# S7CAS-PLEIADES-CARTE-MERE_P01_CAN.net
KiCad netlist of a schematic drawn in Altium Designer
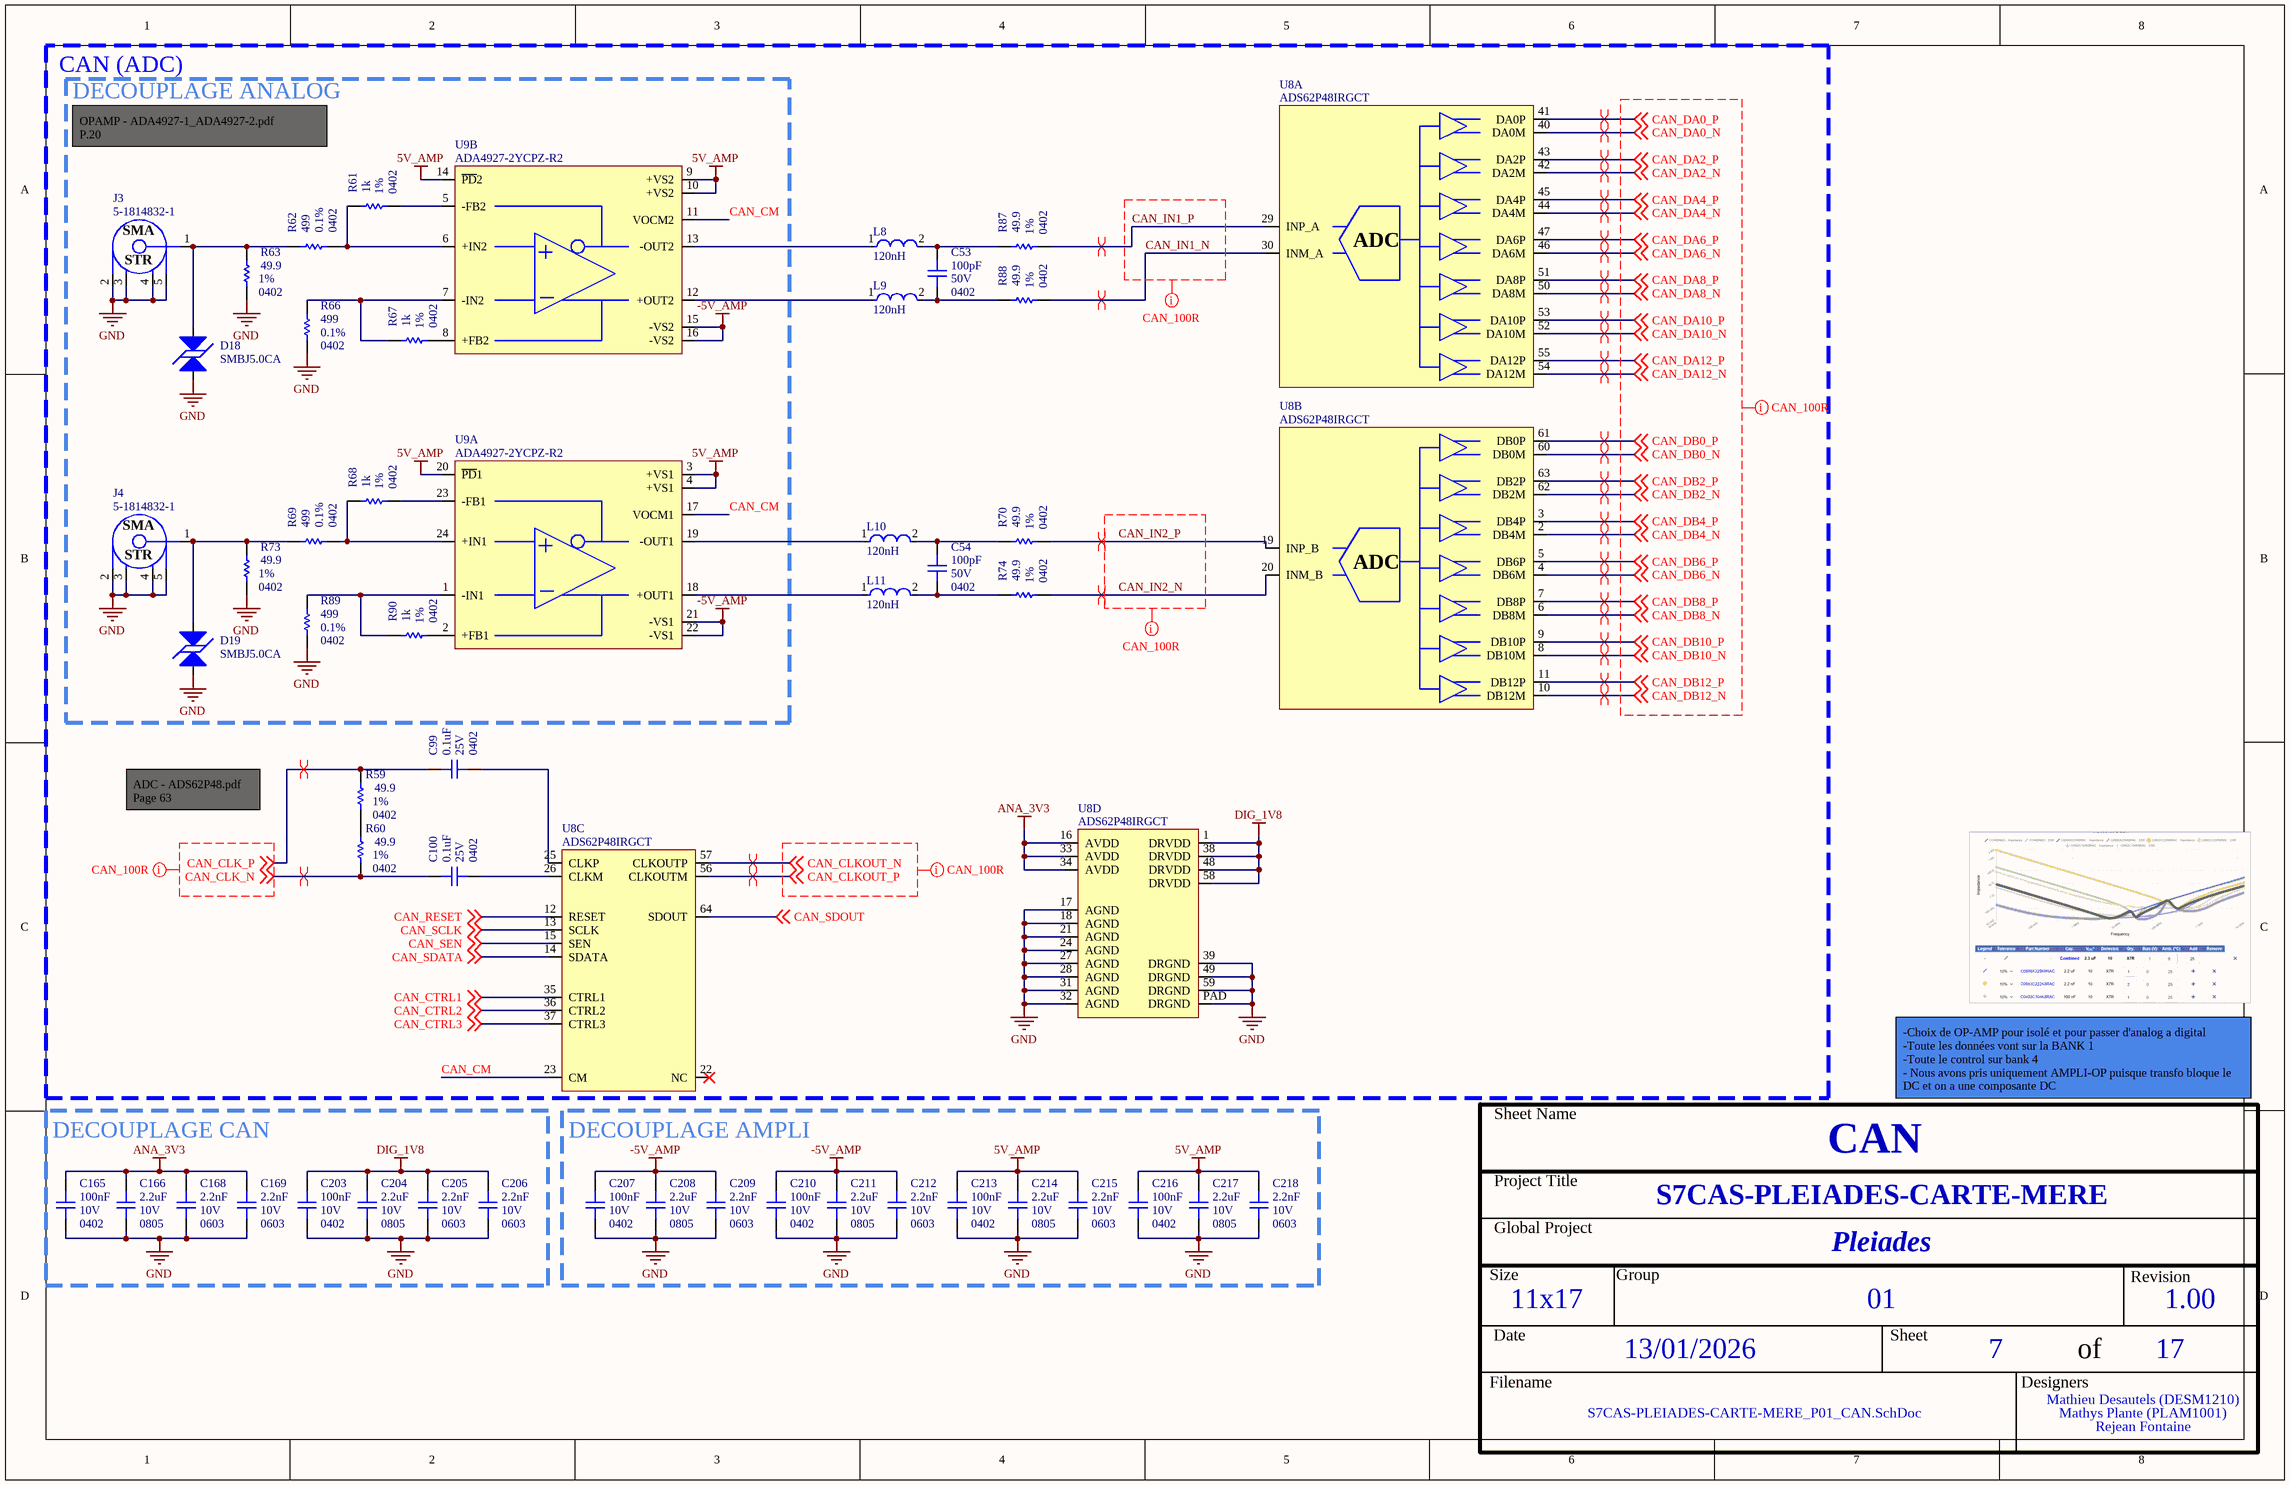
[diagram p0: S7CAS-PLEIADES-CARTE-MERE_P01_CAN.SchDoc]

(export (version "E")
  (design (tool "Eeschema 10.0.6"))
  (components
    (comp (ref "C53")
      (value "100pF")
      (footprint "CAP_0402")
      (description "100 pF ±5% 50V Ceramic Capacitor C0G, NP0 0603 (1608 Metric)")
      (fields
        (field (name "MFG") "Murata Electronics")
        (field (name "MFG PART NUMBER") "GRM1885C1H101JA01D")
        (field (name "VOLTAGE") "50V")
        (field (name "PACKAGE") "0402")
        (field (name "CREATEDBY") "Jonathan Bouchard")
      )
      (libsource (lib "s7cas_lib2023") (part "CAP - 0402"))
    )
    (comp (ref "C54")
      (value "100pF")
      (footprint "CAP_0402")
      (description "100 pF ±5% 50V Ceramic Capacitor C0G, NP0 0603 (1608 Metric)")
      (fields
        (field (name "MFG") "Murata Electronics")
        (field (name "MFG PART NUMBER") "GRM1885C1H101JA01D")
        (field (name "VOLTAGE") "50V")
        (field (name "PACKAGE") "0402")
        (field (name "CREATEDBY") "Jonathan Bouchard")
      )
      (libsource (lib "s7cas_lib2023") (part "CAP - 0402"))
    )
    (comp (ref "C99")
      (value "0.1uF")
      (footprint "CAP_0402")
      (description "0.1 µF ±10% 25V Ceramic Capacitor X7R 0402 (1005 Metric)")
      (fields
        (field (name "MFG") "Samsung Electro-Mechanics")
        (field (name "MFG PART NUMBER") "CL05B104KA5NNNC")
        (field (name "VOLTAGE") "25V")
        (field (name "PACKAGE") "0402")
        (field (name "CREATEDBY") "Jonathan Bouchard")
      )
      (libsource (lib "s7cas_lib2023") (part "CAP - 0402"))
    )
    (comp (ref "C100")
      (value "0.1uF")
      (footprint "CAP_0402")
      (description "0.1 µF ±10% 25V Ceramic Capacitor X7R 0402 (1005 Metric)")
      (fields
        (field (name "MFG") "Samsung Electro-Mechanics")
        (field (name "MFG PART NUMBER") "CL05B104KA5NNNC")
        (field (name "VOLTAGE") "25V")
        (field (name "PACKAGE") "0402")
        (field (name "CREATEDBY") "Jonathan Bouchard")
      )
      (libsource (lib "s7cas_lib2023") (part "CAP - 0402"))
    )
    (comp (ref "C165")
      (value "100nF")
      (footprint "CAP_0402")
      (description "CAP - 0402")
      (fields
        (field (name "MFG PART NUMBER") "C0402C104K8RAC")
        (field (name "VOLTAGE") "10V")
        (field (name "PACKAGE") "0402")
        (field (name "CREATEDBY") "Jonathan Bouchard")
      )
      (libsource (lib "s7cas_lib2023") (part "CAP - 0402"))
    )
    (comp (ref "C166")
      (value "2.2uF")
      (footprint "CAP_0805")
      (description "CAP - 0805")
      (fields
        (field (name "MFG PART NUMBER") "C0805C225K8RAC")
        (field (name "VOLTAGE") "10V")
        (field (name "PACKAGE") "0805")
        (field (name "CREATEDBY") "Jonathan Bouchard")
      )
      (libsource (lib "s7cas_lib2023") (part "CAP - 0805"))
    )
    (comp (ref "C168")
      (value "2.2nF")
      (footprint "CAP_0603")
      (description "CAP - 0603")
      (fields
        (field (name "MFG PART NUMBER") "C0603X222K8RAC")
        (field (name "VOLTAGE") "10V")
        (field (name "PACKAGE") "0603")
        (field (name "CREATEDBY") "Jonathan Bouchard")
      )
      (libsource (lib "s7cas_lib2023") (part "CAP - 0603"))
    )
    (comp (ref "C169")
      (value "2.2nF")
      (footprint "CAP_0603")
      (description "CAP - 0603")
      (fields
        (field (name "MFG PART NUMBER") "C0603X222K8RAC")
        (field (name "VOLTAGE") "10V")
        (field (name "PACKAGE") "0603")
        (field (name "CREATEDBY") "Jonathan Bouchard")
      )
      (libsource (lib "s7cas_lib2023") (part "CAP - 0603"))
    )
    (comp (ref "C203")
      (value "100nF")
      (footprint "CAP_0402")
      (description "CAP - 0402")
      (fields
        (field (name "MFG PART NUMBER") "C0402C104K8RAC")
        (field (name "VOLTAGE") "10V")
        (field (name "PACKAGE") "0402")
        (field (name "CREATEDBY") "Jonathan Bouchard")
      )
      (libsource (lib "s7cas_lib2023") (part "CAP - 0402"))
    )
    (comp (ref "C204")
      (value "2.2uF")
      (footprint "CAP_0805")
      (description "CAP - 0805")
      (fields
        (field (name "MFG PART NUMBER") "C0805C225K8RAC")
        (field (name "VOLTAGE") "10V")
        (field (name "PACKAGE") "0805")
        (field (name "CREATEDBY") "Jonathan Bouchard")
      )
      (libsource (lib "s7cas_lib2023") (part "CAP - 0805"))
    )
    (comp (ref "C205")
      (value "2.2nF")
      (footprint "CAP_0603")
      (description "CAP - 0603")
      (fields
        (field (name "MFG PART NUMBER") "C0603X222K8RAC")
        (field (name "VOLTAGE") "10V")
        (field (name "PACKAGE") "0603")
        (field (name "CREATEDBY") "Jonathan Bouchard")
      )
      (libsource (lib "s7cas_lib2023") (part "CAP - 0603"))
    )
    (comp (ref "C206")
      (value "2.2nF")
      (footprint "CAP_0603")
      (description "CAP - 0603")
      (fields
        (field (name "MFG PART NUMBER") "C0603X222K8RAC")
        (field (name "VOLTAGE") "10V")
        (field (name "PACKAGE") "0603")
        (field (name "CREATEDBY") "Jonathan Bouchard")
      )
      (libsource (lib "s7cas_lib2023") (part "CAP - 0603"))
    )
    (comp (ref "C207")
      (value "100nF")
      (footprint "CAP_0402")
      (description "CAP - 0402")
      (fields
        (field (name "MFG PART NUMBER") "C0402C104K8RAC")
        (field (name "VOLTAGE") "10V")
        (field (name "PACKAGE") "0402")
        (field (name "CREATEDBY") "Jonathan Bouchard")
      )
      (libsource (lib "s7cas_lib2023") (part "CAP - 0402"))
    )
    (comp (ref "C208")
      (value "2.2uF")
      (footprint "CAP_0805")
      (description "CAP - 0805")
      (fields
        (field (name "MFG PART NUMBER") "C0805C225K8RAC")
        (field (name "VOLTAGE") "10V")
        (field (name "PACKAGE") "0805")
        (field (name "CREATEDBY") "Jonathan Bouchard")
      )
      (libsource (lib "s7cas_lib2023") (part "CAP - 0805"))
    )
    (comp (ref "C209")
      (value "2.2nF")
      (footprint "CAP_0603")
      (description "CAP - 0603")
      (fields
        (field (name "MFG PART NUMBER") "C0603X222K8RAC")
        (field (name "VOLTAGE") "10V")
        (field (name "PACKAGE") "0603")
        (field (name "CREATEDBY") "Jonathan Bouchard")
      )
      (libsource (lib "s7cas_lib2023") (part "CAP - 0603"))
    )
    (comp (ref "C210")
      (value "100nF")
      (footprint "CAP_0402")
      (description "CAP - 0402")
      (fields
        (field (name "MFG PART NUMBER") "C0402C104K8RAC")
        (field (name "VOLTAGE") "10V")
        (field (name "PACKAGE") "0402")
        (field (name "CREATEDBY") "Jonathan Bouchard")
      )
      (libsource (lib "s7cas_lib2023") (part "CAP - 0402"))
    )
    (comp (ref "C211")
      (value "2.2uF")
      (footprint "CAP_0805")
      (description "CAP - 0805")
      (fields
        (field (name "MFG PART NUMBER") "C0805C225K8RAC")
        (field (name "VOLTAGE") "10V")
        (field (name "PACKAGE") "0805")
        (field (name "CREATEDBY") "Jonathan Bouchard")
      )
      (libsource (lib "s7cas_lib2023") (part "CAP - 0805"))
    )
    (comp (ref "C212")
      (value "2.2nF")
      (footprint "CAP_0603")
      (description "CAP - 0603")
      (fields
        (field (name "MFG PART NUMBER") "C0603X222K8RAC")
        (field (name "VOLTAGE") "10V")
        (field (name "PACKAGE") "0603")
        (field (name "CREATEDBY") "Jonathan Bouchard")
      )
      (libsource (lib "s7cas_lib2023") (part "CAP - 0603"))
    )
    (comp (ref "C213")
      (value "100nF")
      (footprint "CAP_0402")
      (description "CAP - 0402")
      (fields
        (field (name "MFG PART NUMBER") "C0402C104K8RAC")
        (field (name "VOLTAGE") "10V")
        (field (name "PACKAGE") "0402")
        (field (name "CREATEDBY") "Jonathan Bouchard")
      )
      (libsource (lib "s7cas_lib2023") (part "CAP - 0402"))
    )
    (comp (ref "C214")
      (value "2.2uF")
      (footprint "CAP_0805")
      (description "CAP - 0805")
      (fields
        (field (name "MFG PART NUMBER") "C0805C225K8RAC")
        (field (name "VOLTAGE") "10V")
        (field (name "PACKAGE") "0805")
        (field (name "CREATEDBY") "Jonathan Bouchard")
      )
      (libsource (lib "s7cas_lib2023") (part "CAP - 0805"))
    )
    (comp (ref "C215")
      (value "2.2nF")
      (footprint "CAP_0603")
      (description "CAP - 0603")
      (fields
        (field (name "MFG PART NUMBER") "C0603X222K8RAC")
        (field (name "VOLTAGE") "10V")
        (field (name "PACKAGE") "0603")
        (field (name "CREATEDBY") "Jonathan Bouchard")
      )
      (libsource (lib "s7cas_lib2023") (part "CAP - 0603"))
    )
    (comp (ref "C216")
      (value "100nF")
      (footprint "CAP_0402")
      (description "CAP - 0402")
      (fields
        (field (name "MFG PART NUMBER") "C0402C104K8RAC")
        (field (name "VOLTAGE") "10V")
        (field (name "PACKAGE") "0402")
        (field (name "CREATEDBY") "Jonathan Bouchard")
      )
      (libsource (lib "s7cas_lib2023") (part "CAP - 0402"))
    )
    (comp (ref "C217")
      (value "2.2uF")
      (footprint "CAP_0805")
      (description "CAP - 0805")
      (fields
        (field (name "MFG PART NUMBER") "C0805C225K8RAC")
        (field (name "VOLTAGE") "10V")
        (field (name "PACKAGE") "0805")
        (field (name "CREATEDBY") "Jonathan Bouchard")
      )
      (libsource (lib "s7cas_lib2023") (part "CAP - 0805"))
    )
    (comp (ref "C218")
      (value "2.2nF")
      (footprint "CAP_0603")
      (description "CAP - 0603")
      (fields
        (field (name "MFG PART NUMBER") "C0603X222K8RAC")
        (field (name "VOLTAGE") "10V")
        (field (name "PACKAGE") "0603")
        (field (name "CREATEDBY") "Jonathan Bouchard")
      )
      (libsource (lib "s7cas_lib2023") (part "CAP - 0603"))
    )
    (comp (ref "D18")
      (value "SMBJ5.0CA")
      (footprint "TVS_PWR_SMBJ5.0CA")
      (description "TVS - BIDIR 5V 9.2V 600W - DO214AA")
      (fields
        (field (name "CREATEDBY/DATE") "Jonathan Bouchard - 2019-03-22")
        (field (name "VERIFIEDBY") "Nicolas V. (2019-05-06)")
      )
      (libsource (lib "s7cas_lib2023") (part "TVS_PWR_SMBJ5.0CA"))
    )
    (comp (ref "D19")
      (value "SMBJ5.0CA")
      (footprint "TVS_PWR_SMBJ5.0CA")
      (description "TVS - BIDIR 5V 9.2V 600W - DO214AA")
      (fields
        (field (name "CREATEDBY/DATE") "Jonathan Bouchard - 2019-03-22")
        (field (name "VERIFIEDBY") "Nicolas V. (2019-05-06)")
      )
      (libsource (lib "s7cas_lib2023") (part "TVS_PWR_SMBJ5.0CA"))
    )
    (comp (ref "J3")
      (value "5-1814832-1")
      (footprint "CONN_SMA_5-1814832-1")
      (description "CONN -  SMA JACK STR 50 OHM - TH")
      (fields
        (field (name "MFG") "TE Connectivity AMP Connectors")
        (field (name "CREATEDBY") "Jonathan Bouchard")
      )
      (libsource (lib "s7cas_lib2023") (part "CONN_SMA_5-1814832-1"))
    )
    (comp (ref "J4")
      (value "5-1814832-1")
      (footprint "CONN_SMA_5-1814832-1")
      (description "CONN -  SMA JACK STR 50 OHM - TH")
      (fields
        (field (name "MFG") "TE Connectivity AMP Connectors")
        (field (name "CREATEDBY") "Jonathan Bouchard")
      )
      (libsource (lib "s7cas_lib2023") (part "CONN_SMA_5-1814832-1"))
    )
    (comp (ref "L8")
      (value "120nH")
      (footprint "FP-0603HP-MFG")
      (description "High Q Ceramic Chip Inductors 3.3nH 5% 0.024Ohm 1900mA 0603")
      (fields (field (name "TOLERANCE") "5%"))
      (libsource (lib "Altium Content Vault") (part "725321dda6339637d4d059423bc1c3c"))
    )
    (comp (ref "L9")
      (value "120nH")
      (footprint "FP-0603HP-MFG")
      (description "High Q Ceramic Chip Inductors 3.3nH 5% 0.024Ohm 1900mA 0603")
      (fields (field (name "TOLERANCE") "5%"))
      (libsource (lib "Altium Content Vault") (part "725321dda6339637d4d059423bc1c3c"))
    )
    (comp (ref "L10")
      (value "120nH")
      (footprint "FP-0603HP-MFG")
      (description "High Q Ceramic Chip Inductors 3.3nH 5% 0.024Ohm 1900mA 0603")
      (fields (field (name "TOLERANCE") "5%"))
      (libsource (lib "Altium Content Vault") (part "725321dda6339637d4d059423bc1c3c"))
    )
    (comp (ref "L11")
      (value "120nH")
      (footprint "FP-0603HP-MFG")
      (description "High Q Ceramic Chip Inductors 3.3nH 5% 0.024Ohm 1900mA 0603")
      (fields (field (name "TOLERANCE") "5%"))
      (libsource (lib "Altium Content Vault") (part "725321dda6339637d4d059423bc1c3c"))
    )
    (comp (ref "R59")
      (value "49.9")
      (footprint "RES_0402")
      (description "49.9 Ohms ±1% 0.1W, 1/10W Chip Resistor 0402 (1005 Metric) Automotive AEC-Q200 Thick Film")
      (fields
        (field (name "VOLTAGE") "75V")
        (field (name "MFG") "Vishay Dale")
        (field (name "PACKAGE") "0402")
        (field (name "PRECISION") "1%")
        (field (name "CREATEDBY") "Jonathan Bouchard")
      )
      (libsource (lib "s7cas_lib2023") (part "RES - 0402"))
    )
    (comp (ref "R60")
      (value "49.9")
      (footprint "RES_0402")
      (description "49.9 Ohms ±1% 0.1W, 1/10W Chip Resistor 0402 (1005 Metric) Automotive AEC-Q200 Thick Film")
      (fields
        (field (name "VOLTAGE") "75V")
        (field (name "MFG") "Vishay Dale")
        (field (name "PACKAGE") "0402")
        (field (name "PRECISION") "1%")
        (field (name "CREATEDBY") "Jonathan Bouchard")
      )
      (libsource (lib "s7cas_lib2023") (part "RES - 0402"))
    )
    (comp (ref "R61")
      (value "1k")
      (footprint "RES_0402")
      (description "1 kOhms ±1% 0.1W, 1/10W Chip Resistor 0402 (1005 Metric) Automotive AEC-Q200 Thick Film")
      (fields
        (field (name "VOLTAGE") "50V")
        (field (name "MFG") "Panasonic Electronic Components")
        (field (name "PACKAGE") "0402")
        (field (name "PRECISION") "1%")
        (field (name "CREATEDBY") "Jonathan Bouchard")
      )
      (libsource (lib "s7cas_lib2023") (part "RES - 0402"))
    )
    (comp (ref "R62")
      (value "499")
      (footprint "RES_0402")
      (description "499 Ohms ±0.1% 0.063W, 1/16W Chip Resistor 0402 (1005 Metric) Automotive AEC-Q200 Thin Film")
      (fields
        (field (name "VOLTAGE") "TBD")
        (field (name "MFG") "Panasonic Electronic Components")
        (field (name "PACKAGE") "0402")
        (field (name "PRECISION") "0.1%")
        (field (name "CREATEDBY") "Jonathan Bouchard")
      )
      (libsource (lib "s7cas_lib2023") (part "RES - 0402"))
    )
    (comp (ref "R63")
      (value "49.9")
      (footprint "RES_0402")
      (description "49.9 Ohms ±1% 0.1W, 1/10W Chip Resistor 0402 (1005 Metric) Automotive AEC-Q200 Thick Film")
      (fields
        (field (name "VOLTAGE") "75V")
        (field (name "MFG") "Vishay Dale")
        (field (name "PACKAGE") "0402")
        (field (name "PRECISION") "1%")
        (field (name "CREATEDBY") "Jonathan Bouchard")
      )
      (libsource (lib "s7cas_lib2023") (part "RES - 0402"))
    )
    (comp (ref "R66")
      (value "499")
      (footprint "RES_0402")
      (description "499 Ohms ±0.1% 0.063W, 1/16W Chip Resistor 0402 (1005 Metric) Automotive AEC-Q200 Thin Film")
      (fields
        (field (name "VOLTAGE") "TBD")
        (field (name "MFG") "Panasonic Electronic Components")
        (field (name "PACKAGE") "0402")
        (field (name "PRECISION") "0.1%")
        (field (name "CREATEDBY") "Jonathan Bouchard")
      )
      (libsource (lib "s7cas_lib2023") (part "RES - 0402"))
    )
    (comp (ref "R67")
      (value "1k")
      (footprint "RES_0402")
      (description "1 kOhms ±1% 0.1W, 1/10W Chip Resistor 0402 (1005 Metric) Automotive AEC-Q200 Thick Film")
      (fields
        (field (name "VOLTAGE") "50V")
        (field (name "MFG") "Panasonic Electronic Components")
        (field (name "PACKAGE") "0402")
        (field (name "PRECISION") "1%")
        (field (name "CREATEDBY") "Jonathan Bouchard")
      )
      (libsource (lib "s7cas_lib2023") (part "RES - 0402"))
    )
    (comp (ref "R68")
      (value "1k")
      (footprint "RES_0402")
      (description "1 kOhms ±1% 0.1W, 1/10W Chip Resistor 0402 (1005 Metric) Automotive AEC-Q200 Thick Film")
      (fields
        (field (name "VOLTAGE") "50V")
        (field (name "MFG") "Panasonic Electronic Components")
        (field (name "PACKAGE") "0402")
        (field (name "PRECISION") "1%")
        (field (name "CREATEDBY") "Jonathan Bouchard")
      )
      (libsource (lib "s7cas_lib2023") (part "RES - 0402"))
    )
    (comp (ref "R69")
      (value "499")
      (footprint "RES_0402")
      (description "499 Ohms ±0.1% 0.063W, 1/16W Chip Resistor 0402 (1005 Metric) Automotive AEC-Q200 Thin Film")
      (fields
        (field (name "VOLTAGE") "TBD")
        (field (name "MFG") "Panasonic Electronic Components")
        (field (name "PACKAGE") "0402")
        (field (name "PRECISION") "0.1%")
        (field (name "CREATEDBY") "Jonathan Bouchard")
      )
      (libsource (lib "s7cas_lib2023") (part "RES - 0402"))
    )
    (comp (ref "R70")
      (value "49.9")
      (footprint "RES_0402")
      (description "49.9 Ohms ±1% 0.1W, 1/10W Chip Resistor 0402 (1005 Metric) Automotive AEC-Q200 Thick Film")
      (fields
        (field (name "VOLTAGE") "75V")
        (field (name "MFG") "Vishay Dale")
        (field (name "PACKAGE") "0402")
        (field (name "PRECISION") "1%")
        (field (name "CREATEDBY") "Jonathan Bouchard")
      )
      (libsource (lib "s7cas_lib2023") (part "RES - 0402"))
    )
    (comp (ref "R73")
      (value "49.9")
      (footprint "RES_0402")
      (description "49.9 Ohms ±1% 0.1W, 1/10W Chip Resistor 0402 (1005 Metric) Automotive AEC-Q200 Thick Film")
      (fields
        (field (name "VOLTAGE") "75V")
        (field (name "MFG") "Vishay Dale")
        (field (name "PACKAGE") "0402")
        (field (name "PRECISION") "1%")
        (field (name "CREATEDBY") "Jonathan Bouchard")
      )
      (libsource (lib "s7cas_lib2023") (part "RES - 0402"))
    )
    (comp (ref "R74")
      (value "49.9")
      (footprint "RES_0402")
      (description "49.9 Ohms ±1% 0.1W, 1/10W Chip Resistor 0402 (1005 Metric) Automotive AEC-Q200 Thick Film")
      (fields
        (field (name "VOLTAGE") "75V")
        (field (name "MFG") "Vishay Dale")
        (field (name "PACKAGE") "0402")
        (field (name "PRECISION") "1%")
        (field (name "CREATEDBY") "Jonathan Bouchard")
      )
      (libsource (lib "s7cas_lib2023") (part "RES - 0402"))
    )
    (comp (ref "R87")
      (value "49.9")
      (footprint "RES_0402")
      (description "49.9 Ohms ±1% 0.1W, 1/10W Chip Resistor 0402 (1005 Metric) Automotive AEC-Q200 Thick Film")
      (fields
        (field (name "VOLTAGE") "75V")
        (field (name "MFG") "Vishay Dale")
        (field (name "PACKAGE") "0402")
        (field (name "PRECISION") "1%")
        (field (name "CREATEDBY") "Jonathan Bouchard")
      )
      (libsource (lib "s7cas_lib2023") (part "RES - 0402"))
    )
    (comp (ref "R88")
      (value "49.9")
      (footprint "RES_0402")
      (description "49.9 Ohms ±1% 0.1W, 1/10W Chip Resistor 0402 (1005 Metric) Automotive AEC-Q200 Thick Film")
      (fields
        (field (name "VOLTAGE") "75V")
        (field (name "MFG") "Vishay Dale")
        (field (name "PACKAGE") "0402")
        (field (name "PRECISION") "1%")
        (field (name "CREATEDBY") "Jonathan Bouchard")
      )
      (libsource (lib "s7cas_lib2023") (part "RES - 0402"))
    )
    (comp (ref "R89")
      (value "499")
      (footprint "RES_0402")
      (description "499 Ohms ±0.1% 0.063W, 1/16W Chip Resistor 0402 (1005 Metric) Automotive AEC-Q200 Thin Film")
      (fields
        (field (name "VOLTAGE") "TBD")
        (field (name "MFG") "Panasonic Electronic Components")
        (field (name "PACKAGE") "0402")
        (field (name "PRECISION") "0.1%")
        (field (name "CREATEDBY") "Jonathan Bouchard")
      )
      (libsource (lib "s7cas_lib2023") (part "RES - 0402"))
    )
    (comp (ref "R90")
      (value "1k")
      (footprint "RES_0402")
      (description "1 kOhms ±1% 0.1W, 1/10W Chip Resistor 0402 (1005 Metric) Automotive AEC-Q200 Thick Film")
      (fields
        (field (name "VOLTAGE") "50V")
        (field (name "MFG") "Panasonic Electronic Components")
        (field (name "PACKAGE") "0402")
        (field (name "PRECISION") "1%")
        (field (name "CREATEDBY") "Jonathan Bouchard")
      )
      (libsource (lib "s7cas_lib2023") (part "RES - 0402"))
    )
    (comp (ref "U8")
      (value "ADS62P48IRGCT")
      (footprint "ADC_ADS62P48IRGCT")
      (description "ADC - 14 BIT 210MSPS SUAL - VQFN-64")
      (fields
        (field (name "VOLTAGE") "3.15 V ~ 3.6 V / 1.7 V ~ 1.9 V")
        (field (name "MFG") "Texas Instruments")
        (field (name "CREATEDBY") "Jonathan Bouchard")
      )
      (libsource (lib "s7cas_lib2023") (part "ADC_ADS62P48IRGCT"))
    )
    (comp (ref "U9")
      (value "ADA4927-2YCPZ-R2")
      (footprint "OPAMP_ADA4927-2YCPZ-R2")
      (description "OPAMP - CFA 2.3GHZ - QFN-24")
      (fields
        (field (name "VOLTAGE") "4.5 V ~ 11 V, ±2.25 V ~ 5.5 V")
        (field (name "MFG") "Analog Devices")
        (field (name "CREATEDBY") "Jonathan Bouchard")
      )
      (libsource (lib "s7cas_lib2023") (part "OPAMP_ADA4927-2YCPZ-R2"))
    )
  )
  (nets
    (net (code "1") (name "-5V_AMP") (class "Default")
      (node (ref "C207") (pin "2") (pinfunction "2_2") (pintype "passive"))
      (node (ref "C208") (pin "2") (pinfunction "2_2") (pintype "passive"))
      (node (ref "C209") (pin "2") (pinfunction "2_2") (pintype "passive"))
      (node (ref "C210") (pin "2") (pinfunction "2_2") (pintype "passive"))
      (node (ref "C211") (pin "2") (pinfunction "2_2") (pintype "passive"))
      (node (ref "C212") (pin "2") (pinfunction "2_2") (pintype "passive"))
      (node (ref "U9") (pin "15") (pinfunction "-VS2_15") (pintype "passive"))
      (node (ref "U9") (pin "16") (pinfunction "-VS2_16") (pintype "passive"))
      (node (ref "U9") (pin "21") (pinfunction "-VS1_21") (pintype "passive"))
      (node (ref "U9") (pin "22") (pinfunction "-VS1_22") (pintype "passive"))
    )
    (net (code "2") (name "/CAN_CM") (class "Default")
      (node (ref "U8") (pin "23") (pinfunction "CM_23") (pintype "passive"))
      (node (ref "U9") (pin "11") (pinfunction "VOCM2_11") (pintype "passive"))
      (node (ref "U9") (pin "17") (pinfunction "VOCM1_17") (pintype "passive"))
    )
    (net (code "3") (name "/CAN_IN1_N") (class "Default")
      (node (ref "R88") (pin "1") (pinfunction "1_1") (pintype "passive"))
      (node (ref "U8") (pin "30") (pinfunction "INM_A_30") (pintype "passive"))
    )
    (net (code "4") (name "/CAN_IN1_P") (class "Default")
      (node (ref "R87") (pin "1") (pinfunction "1_1") (pintype "passive"))
      (node (ref "U8") (pin "29") (pinfunction "INP_A_29") (pintype "passive"))
    )
    (net (code "5") (name "/CAN_IN2_N") (class "Default")
      (node (ref "R74") (pin "1") (pinfunction "1_1") (pintype "passive"))
      (node (ref "U8") (pin "20") (pinfunction "INM_B_20") (pintype "passive"))
    )
    (net (code "6") (name "/CAN_IN2_P") (class "Default")
      (node (ref "R70") (pin "1") (pinfunction "1_1") (pintype "passive"))
      (node (ref "U8") (pin "19") (pinfunction "INP_B_19") (pintype "passive"))
    )
    (net (code "7") (name "5V_AMP") (class "Default")
      (node (ref "C213") (pin "2") (pinfunction "2_2") (pintype "passive"))
      (node (ref "C214") (pin "2") (pinfunction "2_2") (pintype "passive"))
      (node (ref "C215") (pin "2") (pinfunction "2_2") (pintype "passive"))
      (node (ref "C216") (pin "2") (pinfunction "2_2") (pintype "passive"))
      (node (ref "C217") (pin "2") (pinfunction "2_2") (pintype "passive"))
      (node (ref "C218") (pin "2") (pinfunction "2_2") (pintype "passive"))
      (node (ref "U9") (pin "10") (pinfunction "+VS2_10") (pintype "passive"))
      (node (ref "U9") (pin "14") (pinfunction "~{PD}2_14") (pintype "passive"))
      (node (ref "U9") (pin "20") (pinfunction "~{PD}1_20") (pintype "passive"))
      (node (ref "U9") (pin "3") (pinfunction "+VS1_3") (pintype "passive"))
      (node (ref "U9") (pin "4") (pinfunction "+VS1_4") (pintype "passive"))
      (node (ref "U9") (pin "9") (pinfunction "+VS2_9") (pintype "passive"))
    )
    (net (code "8") (name "ANA_3V3") (class "Default")
      (node (ref "C165") (pin "2") (pinfunction "2_2") (pintype "passive"))
      (node (ref "C166") (pin "2") (pinfunction "2_2") (pintype "passive"))
      (node (ref "C168") (pin "2") (pinfunction "2_2") (pintype "passive"))
      (node (ref "C169") (pin "2") (pinfunction "2_2") (pintype "passive"))
      (node (ref "U8") (pin "16") (pinfunction "AVDD_16") (pintype "passive"))
      (node (ref "U8") (pin "33") (pinfunction "AVDD_33") (pintype "passive"))
      (node (ref "U8") (pin "34") (pinfunction "AVDD_34") (pintype "passive"))
    )
    (net (code "9") (name "CAN_CLKOUT_N") (class "Default")
      (node (ref "U8") (pin "57") (pinfunction "CLKOUTP_57") (pintype "passive"))
    )
    (net (code "10") (name "CAN_CLKOUT_P") (class "Default")
      (node (ref "U8") (pin "56") (pinfunction "CLKOUTM_56") (pintype "passive"))
    )
    (net (code "11") (name "CAN_CLK_N") (class "Default")
      (node (ref "C100") (pin "2") (pinfunction "2_2") (pintype "passive"))
      (node (ref "R60") (pin "1") (pinfunction "1_1") (pintype "passive"))
    )
    (net (code "12") (name "CAN_CLK_P") (class "Default")
      (node (ref "C99") (pin "2") (pinfunction "2_2") (pintype "passive"))
      (node (ref "R59") (pin "2") (pinfunction "2_2") (pintype "passive"))
    )
    (net (code "13") (name "CAN_CTRL1") (class "Default")
      (node (ref "U8") (pin "35") (pinfunction "CTRL1_35") (pintype "passive"))
    )
    (net (code "14") (name "CAN_CTRL2") (class "Default")
      (node (ref "U8") (pin "36") (pinfunction "CTRL2_36") (pintype "passive"))
    )
    (net (code "15") (name "CAN_CTRL3") (class "Default")
      (node (ref "U8") (pin "37") (pinfunction "CTRL3_37") (pintype "passive"))
    )
    (net (code "16") (name "CAN_DA0_N") (class "Default")
      (node (ref "U8") (pin "40") (pinfunction "DA0M_40") (pintype "passive"))
    )
    (net (code "17") (name "CAN_DA0_P") (class "Default")
      (node (ref "U8") (pin "41") (pinfunction "DA0P_41") (pintype "passive"))
    )
    (net (code "18") (name "CAN_DA2_N") (class "Default")
      (node (ref "U8") (pin "42") (pinfunction "DA2M_42") (pintype "passive"))
    )
    (net (code "19") (name "CAN_DA2_P") (class "Default")
      (node (ref "U8") (pin "43") (pinfunction "DA2P_43") (pintype "passive"))
    )
    (net (code "20") (name "CAN_DA4_N") (class "Default")
      (node (ref "U8") (pin "44") (pinfunction "DA4M_44") (pintype "passive"))
    )
    (net (code "21") (name "CAN_DA4_P") (class "Default")
      (node (ref "U8") (pin "45") (pinfunction "DA4P_45") (pintype "passive"))
    )
    (net (code "22") (name "CAN_DA6_N") (class "Default")
      (node (ref "U8") (pin "46") (pinfunction "DA6M_46") (pintype "passive"))
    )
    (net (code "23") (name "CAN_DA6_P") (class "Default")
      (node (ref "U8") (pin "47") (pinfunction "DA6P_47") (pintype "passive"))
    )
    (net (code "24") (name "CAN_DA8_N") (class "Default")
      (node (ref "U8") (pin "50") (pinfunction "DA8M_50") (pintype "passive"))
    )
    (net (code "25") (name "CAN_DA8_P") (class "Default")
      (node (ref "U8") (pin "51") (pinfunction "DA8P_51") (pintype "passive"))
    )
    (net (code "26") (name "CAN_DA10_N") (class "Default")
      (node (ref "U8") (pin "52") (pinfunction "DA10M_52") (pintype "passive"))
    )
    (net (code "27") (name "CAN_DA10_P") (class "Default")
      (node (ref "U8") (pin "53") (pinfunction "DA10P_53") (pintype "passive"))
    )
    (net (code "28") (name "CAN_DA12_N") (class "Default")
      (node (ref "U8") (pin "54") (pinfunction "DA12M_54") (pintype "passive"))
    )
    (net (code "29") (name "CAN_DA12_P") (class "Default")
      (node (ref "U8") (pin "55") (pinfunction "DA12P_55") (pintype "passive"))
    )
    (net (code "30") (name "CAN_DB0_N") (class "Default")
      (node (ref "U8") (pin "60") (pinfunction "DB0M_60") (pintype "passive"))
    )
    (net (code "31") (name "CAN_DB0_P") (class "Default")
      (node (ref "U8") (pin "61") (pinfunction "DB0P_61") (pintype "passive"))
    )
    (net (code "32") (name "CAN_DB2_N") (class "Default")
      (node (ref "U8") (pin "62") (pinfunction "DB2M_62") (pintype "passive"))
    )
    (net (code "33") (name "CAN_DB2_P") (class "Default")
      (node (ref "U8") (pin "63") (pinfunction "DB2P_63") (pintype "passive"))
    )
    (net (code "34") (name "CAN_DB4_N") (class "Default")
      (node (ref "U8") (pin "2") (pinfunction "DB4M_2") (pintype "passive"))
    )
    (net (code "35") (name "CAN_DB4_P") (class "Default")
      (node (ref "U8") (pin "3") (pinfunction "DB4P_3") (pintype "passive"))
    )
    (net (code "36") (name "CAN_DB6_N") (class "Default")
      (node (ref "U8") (pin "4") (pinfunction "DB6M_4") (pintype "passive"))
    )
    (net (code "37") (name "CAN_DB6_P") (class "Default")
      (node (ref "U8") (pin "5") (pinfunction "DB6P_5") (pintype "passive"))
    )
    (net (code "38") (name "CAN_DB8_N") (class "Default")
      (node (ref "U8") (pin "6") (pinfunction "DB8M_6") (pintype "passive"))
    )
    (net (code "39") (name "CAN_DB8_P") (class "Default")
      (node (ref "U8") (pin "7") (pinfunction "DB8P_7") (pintype "passive"))
    )
    (net (code "40") (name "CAN_DB10_N") (class "Default")
      (node (ref "U8") (pin "8") (pinfunction "DB10M_8") (pintype "passive"))
    )
    (net (code "41") (name "CAN_DB10_P") (class "Default")
      (node (ref "U8") (pin "9") (pinfunction "DB10P_9") (pintype "passive"))
    )
    (net (code "42") (name "CAN_DB12_N") (class "Default")
      (node (ref "U8") (pin "10") (pinfunction "DB12M_10") (pintype "passive"))
    )
    (net (code "43") (name "CAN_DB12_P") (class "Default")
      (node (ref "U8") (pin "11") (pinfunction "DB12P_11") (pintype "passive"))
    )
    (net (code "44") (name "CAN_RESET") (class "Default")
      (node (ref "U8") (pin "12") (pinfunction "RESET_12") (pintype "passive"))
    )
    (net (code "45") (name "CAN_SCLK") (class "Default")
      (node (ref "U8") (pin "13") (pinfunction "SCLK_13") (pintype "passive"))
    )
    (net (code "46") (name "CAN_SDATA") (class "Default")
      (node (ref "U8") (pin "14") (pinfunction "SDATA_14") (pintype "passive"))
    )
    (net (code "47") (name "CAN_SDOUT") (class "Default")
      (node (ref "U8") (pin "64") (pinfunction "SDOUT_64") (pintype "passive"))
    )
    (net (code "48") (name "CAN_SEN") (class "Default")
      (node (ref "U8") (pin "15") (pinfunction "SEN_15") (pintype "passive"))
    )
    (net (code "49") (name "DIG_1V8") (class "Default")
      (node (ref "C203") (pin "2") (pinfunction "2_2") (pintype "passive"))
      (node (ref "C204") (pin "2") (pinfunction "2_2") (pintype "passive"))
      (node (ref "C205") (pin "2") (pinfunction "2_2") (pintype "passive"))
      (node (ref "C206") (pin "2") (pinfunction "2_2") (pintype "passive"))
      (node (ref "U8") (pin "1") (pinfunction "DRVDD_1") (pintype "passive"))
      (node (ref "U8") (pin "38") (pinfunction "DRVDD_38") (pintype "passive"))
      (node (ref "U8") (pin "48") (pinfunction "DRVDD_48") (pintype "passive"))
      (node (ref "U8") (pin "58") (pinfunction "DRVDD_58") (pintype "passive"))
    )
    (net (code "50") (name "GND") (class "Default")
      (node (ref "C165") (pin "1") (pinfunction "1_1") (pintype "passive"))
      (node (ref "C166") (pin "1") (pinfunction "1_1") (pintype "passive"))
      (node (ref "C168") (pin "1") (pinfunction "1_1") (pintype "passive"))
      (node (ref "C169") (pin "1") (pinfunction "1_1") (pintype "passive"))
      (node (ref "C203") (pin "1") (pinfunction "1_1") (pintype "passive"))
      (node (ref "C204") (pin "1") (pinfunction "1_1") (pintype "passive"))
      (node (ref "C205") (pin "1") (pinfunction "1_1") (pintype "passive"))
      (node (ref "C206") (pin "1") (pinfunction "1_1") (pintype "passive"))
      (node (ref "C207") (pin "1") (pinfunction "1_1") (pintype "passive"))
      (node (ref "C208") (pin "1") (pinfunction "1_1") (pintype "passive"))
      (node (ref "C209") (pin "1") (pinfunction "1_1") (pintype "passive"))
      (node (ref "C210") (pin "1") (pinfunction "1_1") (pintype "passive"))
      (node (ref "C211") (pin "1") (pinfunction "1_1") (pintype "passive"))
      (node (ref "C212") (pin "1") (pinfunction "1_1") (pintype "passive"))
      (node (ref "C213") (pin "1") (pinfunction "1_1") (pintype "passive"))
      (node (ref "C214") (pin "1") (pinfunction "1_1") (pintype "passive"))
      (node (ref "C215") (pin "1") (pinfunction "1_1") (pintype "passive"))
      (node (ref "C216") (pin "1") (pinfunction "1_1") (pintype "passive"))
      (node (ref "C217") (pin "1") (pinfunction "1_1") (pintype "passive"))
      (node (ref "C218") (pin "1") (pinfunction "1_1") (pintype "passive"))
      (node (ref "D18") (pin "2") (pinfunction "2_2") (pintype "passive"))
      (node (ref "D19") (pin "2") (pinfunction "2_2") (pintype "passive"))
      (node (ref "J3") (pin "2") (pinfunction "2_2") (pintype "passive"))
      (node (ref "J3") (pin "3") (pinfunction "3_3") (pintype "passive"))
      (node (ref "J3") (pin "4") (pinfunction "4_4") (pintype "passive"))
      (node (ref "J3") (pin "5") (pinfunction "5_5") (pintype "passive"))
      (node (ref "J4") (pin "2") (pinfunction "2_2") (pintype "passive"))
      (node (ref "J4") (pin "3") (pinfunction "3_3") (pintype "passive"))
      (node (ref "J4") (pin "4") (pinfunction "4_4") (pintype "passive"))
      (node (ref "J4") (pin "5") (pinfunction "5_5") (pintype "passive"))
      (node (ref "R63") (pin "1") (pinfunction "1_1") (pintype "passive"))
      (node (ref "R66") (pin "1") (pinfunction "1_1") (pintype "passive"))
      (node (ref "R73") (pin "1") (pinfunction "1_1") (pintype "passive"))
      (node (ref "R89") (pin "1") (pinfunction "1_1") (pintype "passive"))
      (node (ref "U8") (pin "17") (pinfunction "AGND_17") (pintype "passive"))
      (node (ref "U8") (pin "18") (pinfunction "AGND_18") (pintype "passive"))
      (node (ref "U8") (pin "21") (pinfunction "AGND_21") (pintype "passive"))
      (node (ref "U8") (pin "24") (pinfunction "AGND_24") (pintype "passive"))
      (node (ref "U8") (pin "27") (pinfunction "AGND_27") (pintype "passive"))
      (node (ref "U8") (pin "28") (pinfunction "AGND_28") (pintype "passive"))
      (node (ref "U8") (pin "31") (pinfunction "AGND_31") (pintype "passive"))
      (node (ref "U8") (pin "32") (pinfunction "AGND_32") (pintype "passive"))
      (node (ref "U8") (pin "39") (pinfunction "DRGND_39") (pintype "passive"))
      (node (ref "U8") (pin "49") (pinfunction "DRGND_49") (pintype "passive"))
      (node (ref "U8") (pin "59") (pinfunction "DRGND_59") (pintype "passive"))
      (node (ref "U8") (pin "PAD") (pinfunction "DRGND_PAD") (pintype "passive"))
    )
    (net (code "51") (name "Net-(C53-Pad1)") (class "Default")
      (node (ref "C53") (pin "1") (pinfunction "1_1") (pintype "passive"))
      (node (ref "L9") (pin "2") (pinfunction "2_2") (pintype "passive"))
      (node (ref "R88") (pin "2") (pinfunction "2_2") (pintype "passive"))
    )
    (net (code "52") (name "Net-(C53-Pad2)") (class "Default")
      (node (ref "C53") (pin "2") (pinfunction "2_2") (pintype "passive"))
      (node (ref "L8") (pin "2") (pinfunction "2_2") (pintype "passive"))
      (node (ref "R87") (pin "2") (pinfunction "2_2") (pintype "passive"))
    )
    (net (code "53") (name "Net-(C54-Pad1)") (class "Default")
      (node (ref "C54") (pin "1") (pinfunction "1_1") (pintype "passive"))
      (node (ref "L11") (pin "2") (pinfunction "2_2") (pintype "passive"))
      (node (ref "R74") (pin "2") (pinfunction "2_2") (pintype "passive"))
    )
    (net (code "54") (name "Net-(C54-Pad2)") (class "Default")
      (node (ref "C54") (pin "2") (pinfunction "2_2") (pintype "passive"))
      (node (ref "L10") (pin "2") (pinfunction "2_2") (pintype "passive"))
      (node (ref "R70") (pin "2") (pinfunction "2_2") (pintype "passive"))
    )
    (net (code "55") (name "Net-(D18-Pad1)") (class "Default")
      (node (ref "D18") (pin "1") (pinfunction "1_1") (pintype "passive"))
      (node (ref "J3") (pin "1") (pinfunction "1_1") (pintype "passive"))
      (node (ref "R62") (pin "2") (pinfunction "2_2") (pintype "passive"))
      (node (ref "R63") (pin "2") (pinfunction "2_2") (pintype "passive"))
    )
    (net (code "56") (name "Net-(D19-Pad1)") (class "Default")
      (node (ref "D19") (pin "1") (pinfunction "1_1") (pintype "passive"))
      (node (ref "J4") (pin "1") (pinfunction "1_1") (pintype "passive"))
      (node (ref "R69") (pin "2") (pinfunction "2_2") (pintype "passive"))
      (node (ref "R73") (pin "2") (pinfunction "2_2") (pintype "passive"))
    )
    (net (code "57") (name "Net-(R59-Pad1)") (class "Default")
      (node (ref "R59") (pin "1") (pinfunction "1_1") (pintype "passive"))
      (node (ref "R60") (pin "2") (pinfunction "2_2") (pintype "passive"))
    )
    (net (code "58") (name "Net-(U8C-CLKM)") (class "Default")
      (node (ref "C100") (pin "1") (pinfunction "1_1") (pintype "passive"))
      (node (ref "U8") (pin "26") (pinfunction "CLKM_26") (pintype "passive"))
    )
    (net (code "59") (name "Net-(U8C-CLKP)") (class "Default")
      (node (ref "C99") (pin "1") (pinfunction "1_1") (pintype "passive"))
      (node (ref "U8") (pin "25") (pinfunction "CLKP_25") (pintype "passive"))
    )
    (net (code "60") (name "Net-(U9A-+FB1)") (class "Default")
      (node (ref "R90") (pin "1") (pinfunction "1_1") (pintype "passive"))
      (node (ref "U9") (pin "2") (pinfunction "+FB1_2") (pintype "passive"))
    )
    (net (code "61") (name "Net-(U9A-+IN1)") (class "Default")
      (node (ref "R68") (pin "2") (pinfunction "2_2") (pintype "passive"))
      (node (ref "R69") (pin "1") (pinfunction "1_1") (pintype "passive"))
      (node (ref "U9") (pin "24") (pinfunction "+IN1_24") (pintype "passive"))
    )
    (net (code "62") (name "Net-(U9A-+OUT1)") (class "Default")
      (node (ref "L11") (pin "1") (pinfunction "1_1") (pintype "passive"))
      (node (ref "U9") (pin "18") (pinfunction "+OUT1_18") (pintype "passive"))
    )
    (net (code "63") (name "Net-(U9A--FB1)") (class "Default")
      (node (ref "R68") (pin "1") (pinfunction "1_1") (pintype "passive"))
      (node (ref "U9") (pin "23") (pinfunction "-FB1_23") (pintype "passive"))
    )
    (net (code "64") (name "Net-(U9A--IN1)") (class "Default")
      (node (ref "R89") (pin "2") (pinfunction "2_2") (pintype "passive"))
      (node (ref "R90") (pin "2") (pinfunction "2_2") (pintype "passive"))
      (node (ref "U9") (pin "1") (pinfunction "-IN1_1") (pintype "passive"))
    )
    (net (code "65") (name "Net-(U9A--OUT1)") (class "Default")
      (node (ref "L10") (pin "1") (pinfunction "1_1") (pintype "passive"))
      (node (ref "U9") (pin "19") (pinfunction "-OUT1_19") (pintype "passive"))
    )
    (net (code "66") (name "Net-(U9B-+FB2)") (class "Default")
      (node (ref "R67") (pin "1") (pinfunction "1_1") (pintype "passive"))
      (node (ref "U9") (pin "8") (pinfunction "+FB2_8") (pintype "passive"))
    )
    (net (code "67") (name "Net-(U9B-+IN2)") (class "Default")
      (node (ref "R61") (pin "2") (pinfunction "2_2") (pintype "passive"))
      (node (ref "R62") (pin "1") (pinfunction "1_1") (pintype "passive"))
      (node (ref "U9") (pin "6") (pinfunction "+IN2_6") (pintype "passive"))
    )
    (net (code "68") (name "Net-(U9B-+OUT2)") (class "Default")
      (node (ref "L9") (pin "1") (pinfunction "1_1") (pintype "passive"))
      (node (ref "U9") (pin "12") (pinfunction "+OUT2_12") (pintype "passive"))
    )
    (net (code "69") (name "Net-(U9B--FB2)") (class "Default")
      (node (ref "R61") (pin "1") (pinfunction "1_1") (pintype "passive"))
      (node (ref "U9") (pin "5") (pinfunction "-FB2_5") (pintype "passive"))
    )
    (net (code "70") (name "Net-(U9B--IN2)") (class "Default")
      (node (ref "R66") (pin "2") (pinfunction "2_2") (pintype "passive"))
      (node (ref "R67") (pin "2") (pinfunction "2_2") (pintype "passive"))
      (node (ref "U9") (pin "7") (pinfunction "-IN2_7") (pintype "passive"))
    )
    (net (code "71") (name "Net-(U9B--OUT2)") (class "Default")
      (node (ref "L8") (pin "1") (pinfunction "1_1") (pintype "passive"))
      (node (ref "U9") (pin "13") (pinfunction "-OUT2_13") (pintype "passive"))
    )
    (net (code "72") (name "unconnected-(U8C-NC-Pad22)") (class "Default")
      (node (ref "U8") (pin "22") (pinfunction "NC_22") (pintype "passive+no_connect"))
    )
  )
)
